# wifi_lamp_01.net
KiCad netlist of a schematic drawn in Altium Designer
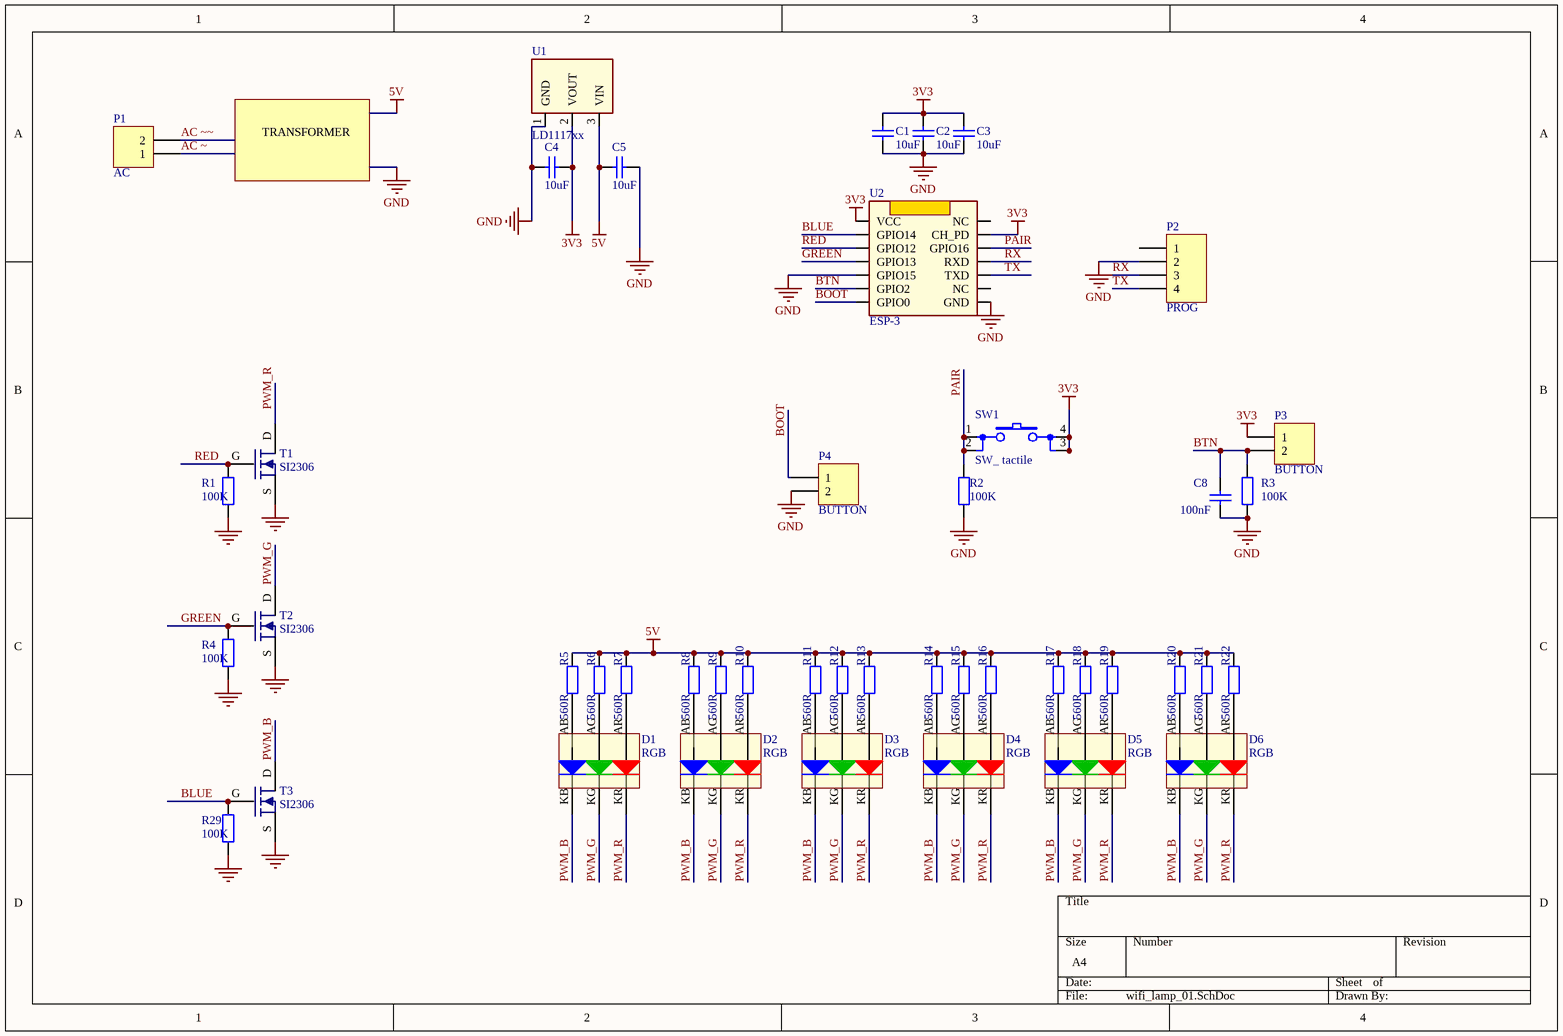
[diagram p0: wifi_lamp_01.SchDoc]

(export (version "E")
  (design (tool "Eeschema 10.0.6"))
  (components
    (comp (ref "C1")
      (value "10uF")
      (footprint "FP_1206_CAP_085")
      (description "Capacitor")
      (fields (field (name "PUBLISHER") "Altium Limited"))
      (libsource (lib "Miscellaneous Devices") (part "Cap"))
    )
    (comp (ref "C2")
      (value "10uF")
      (footprint "FP_1206_CAP_085")
      (description "Capacitor")
      (fields (field (name "PUBLISHER") "Altium Limited"))
      (libsource (lib "Miscellaneous Devices") (part "Cap"))
    )
    (comp (ref "C3")
      (value "10uF")
      (footprint "FP_1206_CAP_085")
      (description "Capacitor")
      (fields (field (name "PUBLISHER") "Altium Limited"))
      (libsource (lib "Miscellaneous Devices") (part "Cap"))
    )
    (comp (ref "C4")
      (value "10uF")
      (footprint "FP_1206_CAP_085")
      (description "Capacitor")
      (fields (field (name "PUBLISHER") "Altium Limited"))
      (libsource (lib "Miscellaneous Devices") (part "Cap"))
    )
    (comp (ref "C5")
      (value "10uF")
      (footprint "FP_1206_CAP_085")
      (description "Capacitor")
      (fields (field (name "PUBLISHER") "Altium Limited"))
      (libsource (lib "Miscellaneous Devices") (part "Cap"))
    )
    (comp (ref "C8")
      (value "100nF")
      (footprint "FP_0603_CAP_080")
      (description "Capacitor")
      (libsource (lib "Miscellaneous Devices") (part "Cap"))
    )
    (comp (ref "D1")
      (value "RGB")
      (footprint "RGB_LED_5.0x5.0mm")
      (description "LED_RGB_6_PIN")
      (libsource (lib "Led_optical") (part "LED_RGB_6_PIN"))
    )
    (comp (ref "D2")
      (value "RGB")
      (footprint "RGB_LED_5.0x5.0mm")
      (description "LED_RGB_6_PIN")
      (libsource (lib "Led_optical") (part "LED_RGB_6_PIN"))
    )
    (comp (ref "D3")
      (value "RGB")
      (footprint "RGB_LED_5.0x5.0mm")
      (description "LED_RGB_6_PIN")
      (libsource (lib "Led_optical") (part "LED_RGB_6_PIN"))
    )
    (comp (ref "D4")
      (value "RGB")
      (footprint "RGB_LED_5.0x5.0mm")
      (description "LED_RGB_6_PIN")
      (libsource (lib "Led_optical") (part "LED_RGB_6_PIN"))
    )
    (comp (ref "D5")
      (value "RGB")
      (footprint "RGB_LED_5.0x5.0mm")
      (description "LED_RGB_6_PIN")
      (libsource (lib "Led_optical") (part "LED_RGB_6_PIN"))
    )
    (comp (ref "D6")
      (value "RGB")
      (footprint "RGB_LED_5.0x5.0mm")
      (description "LED_RGB_6_PIN")
      (libsource (lib "Led_optical") (part "LED_RGB_6_PIN"))
    )
    (comp (ref "P1")
      (value "AC")
      (footprint "Sorkapocs 2P 5mm")
      (description "Header, 2-Pin")
      (fields (field (name "PUBLISHER") "Altium Limited"))
      (libsource (lib "") (part "Header 2_1"))
    )
    (comp (ref "P2")
      (value "PROG")
      (footprint "HDR1X4")
      (description "Header, 4-Pin")
      (fields (field (name "PUBLISHER") "Altium Limited"))
      (libsource (lib "Miscellaneous Connectors") (part "Header 4"))
    )
    (comp (ref "P3")
      (value "BUTTON")
      (footprint "HDR1X2")
      (description "Header, 2-Pin")
      (fields (field (name "PUBLISHER") "Altium Limited"))
      (libsource (lib "Miscellaneous Connectors") (part "Header 2"))
    )
    (comp (ref "P4")
      (value "BUTTON")
      (footprint "HDR1X2")
      (description "Header, 2-Pin")
      (fields (field (name "PUBLISHER") "Altium Limited"))
      (libsource (lib "Miscellaneous Connectors") (part "Header 2"))
    )
    (comp (ref "R1")
      (value "100K")
      (footprint "FP_0603_RES")
      (description "Resistor")
      (libsource (lib "Resistor") (part "RES"))
    )
    (comp (ref "R2")
      (value "100K")
      (footprint "FP_0603_RES")
      (description "Resistor")
      (libsource (lib "") (part "RES_1"))
    )
    (comp (ref "R3")
      (value "100K")
      (footprint "FP_0603_RES")
      (description "Resistor")
      (libsource (lib "Resistor") (part "RES"))
    )
    (comp (ref "R4")
      (value "100K")
      (footprint "FP_0603_RES")
      (description "Resistor")
      (libsource (lib "Resistor") (part "RES"))
    )
    (comp (ref "R5")
      (value "560R")
      (footprint "FP_0603_RES")
      (description "Resistor")
      (libsource (lib "Miscellaneous Devices") (part "Res3"))
    )
    (comp (ref "R6")
      (value "560R")
      (footprint "FP_0603_RES")
      (description "Resistor")
      (libsource (lib "Miscellaneous Devices") (part "Res3"))
    )
    (comp (ref "R7")
      (value "560R")
      (footprint "FP_0603_RES")
      (description "Resistor")
      (libsource (lib "Miscellaneous Devices") (part "Res3"))
    )
    (comp (ref "R8")
      (value "560R")
      (footprint "FP_0603_RES")
      (description "Resistor")
      (libsource (lib "Miscellaneous Devices") (part "Res3"))
    )
    (comp (ref "R9")
      (value "560R")
      (footprint "FP_0603_RES")
      (description "Resistor")
      (libsource (lib "Miscellaneous Devices") (part "Res3"))
    )
    (comp (ref "R10")
      (value "560R")
      (footprint "FP_0603_RES")
      (description "Resistor")
      (libsource (lib "Miscellaneous Devices") (part "Res3"))
    )
    (comp (ref "R11")
      (value "560R")
      (footprint "FP_0603_RES")
      (description "Resistor")
      (libsource (lib "Miscellaneous Devices") (part "Res3"))
    )
    (comp (ref "R12")
      (value "560R")
      (footprint "FP_0603_RES")
      (description "Resistor")
      (libsource (lib "Miscellaneous Devices") (part "Res3"))
    )
    (comp (ref "R13")
      (value "560R")
      (footprint "FP_0603_RES")
      (description "Resistor")
      (libsource (lib "Miscellaneous Devices") (part "Res3"))
    )
    (comp (ref "R14")
      (value "560R")
      (footprint "FP_0603_RES")
      (description "Resistor")
      (libsource (lib "Miscellaneous Devices") (part "Res3"))
    )
    (comp (ref "R15")
      (value "560R")
      (footprint "FP_0603_RES")
      (description "Resistor")
      (libsource (lib "Miscellaneous Devices") (part "Res3"))
    )
    (comp (ref "R16")
      (value "560R")
      (footprint "FP_0603_RES")
      (description "Resistor")
      (libsource (lib "Miscellaneous Devices") (part "Res3"))
    )
    (comp (ref "R17")
      (value "560R")
      (footprint "FP_0603_RES")
      (description "Resistor")
      (libsource (lib "Miscellaneous Devices") (part "Res3"))
    )
    (comp (ref "R18")
      (value "560R")
      (footprint "FP_0603_RES")
      (description "Resistor")
      (libsource (lib "Miscellaneous Devices") (part "Res3"))
    )
    (comp (ref "R19")
      (value "560R")
      (footprint "FP_0603_RES")
      (description "Resistor")
      (libsource (lib "Miscellaneous Devices") (part "Res3"))
    )
    (comp (ref "R20")
      (value "560R")
      (footprint "FP_0603_RES")
      (description "Resistor")
      (libsource (lib "Miscellaneous Devices") (part "Res3"))
    )
    (comp (ref "R21")
      (value "560R")
      (footprint "FP_0603_RES")
      (description "Resistor")
      (libsource (lib "Miscellaneous Devices") (part "Res3"))
    )
    (comp (ref "R22")
      (value "560R")
      (footprint "FP_0603_RES")
      (description "Resistor")
      (libsource (lib "Miscellaneous Devices") (part "Res3"))
    )
    (comp (ref "R29")
      (value "100K")
      (footprint "FP_0603_RES")
      (description "Resistor")
      (libsource (lib "Resistor") (part "RES"))
    )
    (comp (ref "SW1")
      (value "SW_ tactile")
      (footprint "FP_TACTBTN")
      (libsource (lib "Switch") (part "SW_ tactile"))
    )
    (comp (ref "T1") (value "SI2306") (footprint "FET_SOT23") (libsource (lib "FET") (part "NMOS")))
    (comp (ref "T2") (value "SI2306") (footprint "FET_SOT23") (libsource (lib "FET") (part "NMOS")))
    (comp (ref "T3") (value "SI2306") (footprint "FET_SOT23") (libsource (lib "FET") (part "NMOS")))
    (comp (ref "U1")
      (value "LD1117xx")
      (footprint "SUPPLY_SOT223")
      (description "LD1117xx 3,3V lin reg")
      (libsource (lib "Supply") (part "LD1117xx"))
    )
    (comp (ref "U2")
      (value "ESP-3")
      (footprint "ESP_3")
      (description "ESP-3wifi module")
      (libsource (lib "Modul") (part "ESP-3"))
    )
  )
  (nets
    (net (code "1") (name "/AC ~") (class "Default")
      (node (ref "P1") (pin "1") (pinfunction "1_1") (pintype "passive"))
    )
    (net (code "2") (name "/AC ~~") (class "Default")
      (node (ref "P1") (pin "2") (pinfunction "2_2") (pintype "passive"))
    )
    (net (code "3") (name "/BLUE") (class "Default")
      (node (ref "R29") (pin "2") (pinfunction "2_2") (pintype "passive"))
      (node (ref "T3") (pin "G") (pinfunction "G_G") (pintype "passive"))
      (node (ref "U2") (pin "2") (pinfunction "GPIO14_2") (pintype "passive"))
    )
    (net (code "4") (name "/BOOT") (class "Default")
      (node (ref "P4") (pin "1") (pinfunction "1_1") (pintype "passive"))
      (node (ref "U2") (pin "7") (pinfunction "GPIO0_7") (pintype "passive"))
    )
    (net (code "5") (name "/BTN") (class "Default")
      (node (ref "C8") (pin "1") (pinfunction "1_1") (pintype "passive"))
      (node (ref "P3") (pin "2") (pinfunction "2_2") (pintype "passive"))
      (node (ref "R3") (pin "2") (pinfunction "2_2") (pintype "passive"))
      (node (ref "U2") (pin "6") (pinfunction "GPIO2_6") (pintype "passive"))
    )
    (net (code "6") (name "/GREEN") (class "Default")
      (node (ref "R4") (pin "2") (pinfunction "2_2") (pintype "passive"))
      (node (ref "T2") (pin "G") (pinfunction "G_G") (pintype "passive"))
      (node (ref "U2") (pin "4") (pinfunction "GPIO13_4") (pintype "passive"))
    )
    (net (code "7") (name "/PAIR") (class "Default")
      (node (ref "R2") (pin "1") (pinfunction "1_1") (pintype "passive"))
      (node (ref "SW1") (pin "1") (pinfunction "1_1") (pintype "passive"))
      (node (ref "SW1") (pin "2") (pinfunction "2_2") (pintype "passive"))
      (node (ref "U2") (pin "12") (pinfunction "GPIO16_12") (pintype "passive"))
    )
    (net (code "8") (name "/PWM_B") (class "Default")
      (node (ref "D1") (pin "KB") (pinfunction "R_KB") (pintype "passive"))
      (node (ref "D2") (pin "KB") (pinfunction "R_KB") (pintype "passive"))
      (node (ref "D3") (pin "KB") (pinfunction "R_KB") (pintype "passive"))
      (node (ref "D4") (pin "KB") (pinfunction "R_KB") (pintype "passive"))
      (node (ref "D5") (pin "KB") (pinfunction "R_KB") (pintype "passive"))
      (node (ref "D6") (pin "KB") (pinfunction "R_KB") (pintype "passive"))
      (node (ref "T3") (pin "D") (pinfunction "D_D") (pintype "passive"))
    )
    (net (code "9") (name "/PWM_G") (class "Default")
      (node (ref "D1") (pin "KG") (pinfunction "G_KG") (pintype "passive"))
      (node (ref "D2") (pin "KG") (pinfunction "G_KG") (pintype "passive"))
      (node (ref "D3") (pin "KG") (pinfunction "G_KG") (pintype "passive"))
      (node (ref "D4") (pin "KG") (pinfunction "G_KG") (pintype "passive"))
      (node (ref "D5") (pin "KG") (pinfunction "G_KG") (pintype "passive"))
      (node (ref "D6") (pin "KG") (pinfunction "G_KG") (pintype "passive"))
      (node (ref "T2") (pin "D") (pinfunction "D_D") (pintype "passive"))
    )
    (net (code "10") (name "/PWM_R") (class "Default")
      (node (ref "D1") (pin "KR") (pinfunction "B_KR") (pintype "passive"))
      (node (ref "D2") (pin "KR") (pinfunction "B_KR") (pintype "passive"))
      (node (ref "D3") (pin "KR") (pinfunction "B_KR") (pintype "passive"))
      (node (ref "D4") (pin "KR") (pinfunction "B_KR") (pintype "passive"))
      (node (ref "D5") (pin "KR") (pinfunction "B_KR") (pintype "passive"))
      (node (ref "D6") (pin "KR") (pinfunction "B_KR") (pintype "passive"))
      (node (ref "T1") (pin "D") (pinfunction "D_D") (pintype "passive"))
    )
    (net (code "11") (name "/RED") (class "Default")
      (node (ref "R1") (pin "2") (pinfunction "2_2") (pintype "passive"))
      (node (ref "T1") (pin "G") (pinfunction "G_G") (pintype "passive"))
      (node (ref "U2") (pin "3") (pinfunction "GPIO12_3") (pintype "passive"))
    )
    (net (code "12") (name "/RX") (class "Default")
      (node (ref "P2") (pin "3") (pinfunction "3_3") (pintype "passive"))
      (node (ref "U2") (pin "11") (pinfunction "RXD_11") (pintype "passive"))
    )
    (net (code "13") (name "/TX") (class "Default")
      (node (ref "P2") (pin "4") (pinfunction "4_4") (pintype "passive"))
      (node (ref "U2") (pin "10") (pinfunction "TXD_10") (pintype "passive"))
    )
    (net (code "14") (name "3V3") (class "Default")
      (node (ref "C1") (pin "2") (pinfunction "2_2") (pintype "passive"))
      (node (ref "C2") (pin "2") (pinfunction "2_2") (pintype "passive"))
      (node (ref "C3") (pin "2") (pinfunction "2_2") (pintype "passive"))
      (node (ref "C4") (pin "2") (pinfunction "2_2") (pintype "passive"))
      (node (ref "P3") (pin "1") (pinfunction "1_1") (pintype "passive"))
      (node (ref "SW1") (pin "3") (pinfunction "3_3") (pintype "passive"))
      (node (ref "SW1") (pin "4") (pinfunction "4_4") (pintype "passive"))
      (node (ref "U1") (pin "2") (pinfunction "VOUT_2") (pintype "passive"))
      (node (ref "U2") (pin "1") (pinfunction "VCC_1") (pintype "passive"))
      (node (ref "U2") (pin "13") (pinfunction "CH_PD_13") (pintype "passive"))
    )
    (net (code "15") (name "5V") (class "Default")
      (node (ref "C5") (pin "1") (pinfunction "1_1") (pintype "passive"))
      (node (ref "R10") (pin "2") (pinfunction "2_2") (pintype "passive"))
      (node (ref "R11") (pin "2") (pinfunction "2_2") (pintype "passive"))
      (node (ref "R12") (pin "2") (pinfunction "2_2") (pintype "passive"))
      (node (ref "R13") (pin "2") (pinfunction "2_2") (pintype "passive"))
      (node (ref "R14") (pin "2") (pinfunction "2_2") (pintype "passive"))
      (node (ref "R15") (pin "2") (pinfunction "2_2") (pintype "passive"))
      (node (ref "R16") (pin "2") (pinfunction "2_2") (pintype "passive"))
      (node (ref "R17") (pin "2") (pinfunction "2_2") (pintype "passive"))
      (node (ref "R18") (pin "2") (pinfunction "2_2") (pintype "passive"))
      (node (ref "R19") (pin "2") (pinfunction "2_2") (pintype "passive"))
      (node (ref "R20") (pin "2") (pinfunction "2_2") (pintype "passive"))
      (node (ref "R21") (pin "2") (pinfunction "2_2") (pintype "passive"))
      (node (ref "R22") (pin "2") (pinfunction "2_2") (pintype "passive"))
      (node (ref "R5") (pin "2") (pinfunction "2_2") (pintype "passive"))
      (node (ref "R6") (pin "2") (pinfunction "2_2") (pintype "passive"))
      (node (ref "R7") (pin "2") (pinfunction "2_2") (pintype "passive"))
      (node (ref "R8") (pin "2") (pinfunction "2_2") (pintype "passive"))
      (node (ref "R9") (pin "2") (pinfunction "2_2") (pintype "passive"))
      (node (ref "U1") (pin "3") (pinfunction "VIN_3") (pintype "passive"))
    )
    (net (code "16") (name "GND") (class "Default")
      (node (ref "C1") (pin "1") (pinfunction "1_1") (pintype "passive"))
      (node (ref "C2") (pin "1") (pinfunction "1_1") (pintype "passive"))
      (node (ref "C3") (pin "1") (pinfunction "1_1") (pintype "passive"))
      (node (ref "C4") (pin "1") (pinfunction "1_1") (pintype "passive"))
      (node (ref "C5") (pin "2") (pinfunction "2_2") (pintype "passive"))
      (node (ref "C8") (pin "2") (pinfunction "2_2") (pintype "passive"))
      (node (ref "P2") (pin "2") (pinfunction "2_2") (pintype "passive"))
      (node (ref "P4") (pin "2") (pinfunction "2_2") (pintype "passive"))
      (node (ref "R1") (pin "1") (pinfunction "1_1") (pintype "passive"))
      (node (ref "R2") (pin "2") (pinfunction "2_2") (pintype "passive"))
      (node (ref "R29") (pin "1") (pinfunction "1_1") (pintype "passive"))
      (node (ref "R3") (pin "1") (pinfunction "1_1") (pintype "passive"))
      (node (ref "R4") (pin "1") (pinfunction "1_1") (pintype "passive"))
      (node (ref "T1") (pin "S") (pinfunction "S_S") (pintype "passive"))
      (node (ref "T2") (pin "S") (pinfunction "S_S") (pintype "passive"))
      (node (ref "T3") (pin "S") (pinfunction "S_S") (pintype "passive"))
      (node (ref "U1") (pin "1") (pinfunction "GND_1") (pintype "passive"))
      (node (ref "U2") (pin "5") (pinfunction "GPIO15_5") (pintype "passive"))
      (node (ref "U2") (pin "8") (pinfunction "GND_8") (pintype "passive"))
    )
    (net (code "17") (name "Net-(D1-A-PadAB)") (class "Default")
      (node (ref "D1") (pin "AB") (pinfunction "A_AB") (pintype "passive"))
      (node (ref "R5") (pin "1") (pinfunction "1_1") (pintype "passive"))
    )
    (net (code "18") (name "Net-(D1-A-PadAG)") (class "Default")
      (node (ref "D1") (pin "AG") (pinfunction "A_AG") (pintype "passive"))
      (node (ref "R6") (pin "1") (pinfunction "1_1") (pintype "passive"))
    )
    (net (code "19") (name "Net-(D1-A-PadAR)") (class "Default")
      (node (ref "D1") (pin "AR") (pinfunction "A_AR") (pintype "passive"))
      (node (ref "R7") (pin "1") (pinfunction "1_1") (pintype "passive"))
    )
    (net (code "20") (name "Net-(D2-A-PadAB)") (class "Default")
      (node (ref "D2") (pin "AB") (pinfunction "A_AB") (pintype "passive"))
      (node (ref "R8") (pin "1") (pinfunction "1_1") (pintype "passive"))
    )
    (net (code "21") (name "Net-(D2-A-PadAG)") (class "Default")
      (node (ref "D2") (pin "AG") (pinfunction "A_AG") (pintype "passive"))
      (node (ref "R9") (pin "1") (pinfunction "1_1") (pintype "passive"))
    )
    (net (code "22") (name "Net-(D2-A-PadAR)") (class "Default")
      (node (ref "D2") (pin "AR") (pinfunction "A_AR") (pintype "passive"))
      (node (ref "R10") (pin "1") (pinfunction "1_1") (pintype "passive"))
    )
    (net (code "23") (name "Net-(D3-A-PadAB)") (class "Default")
      (node (ref "D3") (pin "AB") (pinfunction "A_AB") (pintype "passive"))
      (node (ref "R11") (pin "1") (pinfunction "1_1") (pintype "passive"))
    )
    (net (code "24") (name "Net-(D3-A-PadAG)") (class "Default")
      (node (ref "D3") (pin "AG") (pinfunction "A_AG") (pintype "passive"))
      (node (ref "R12") (pin "1") (pinfunction "1_1") (pintype "passive"))
    )
    (net (code "25") (name "Net-(D3-A-PadAR)") (class "Default")
      (node (ref "D3") (pin "AR") (pinfunction "A_AR") (pintype "passive"))
      (node (ref "R13") (pin "1") (pinfunction "1_1") (pintype "passive"))
    )
    (net (code "26") (name "Net-(D4-A-PadAB)") (class "Default")
      (node (ref "D4") (pin "AB") (pinfunction "A_AB") (pintype "passive"))
      (node (ref "R14") (pin "1") (pinfunction "1_1") (pintype "passive"))
    )
    (net (code "27") (name "Net-(D4-A-PadAG)") (class "Default")
      (node (ref "D4") (pin "AG") (pinfunction "A_AG") (pintype "passive"))
      (node (ref "R15") (pin "1") (pinfunction "1_1") (pintype "passive"))
    )
    (net (code "28") (name "Net-(D4-A-PadAR)") (class "Default")
      (node (ref "D4") (pin "AR") (pinfunction "A_AR") (pintype "passive"))
      (node (ref "R16") (pin "1") (pinfunction "1_1") (pintype "passive"))
    )
    (net (code "29") (name "Net-(D5-A-PadAB)") (class "Default")
      (node (ref "D5") (pin "AB") (pinfunction "A_AB") (pintype "passive"))
      (node (ref "R17") (pin "1") (pinfunction "1_1") (pintype "passive"))
    )
    (net (code "30") (name "Net-(D5-A-PadAG)") (class "Default")
      (node (ref "D5") (pin "AG") (pinfunction "A_AG") (pintype "passive"))
      (node (ref "R18") (pin "1") (pinfunction "1_1") (pintype "passive"))
    )
    (net (code "31") (name "Net-(D5-A-PadAR)") (class "Default")
      (node (ref "D5") (pin "AR") (pinfunction "A_AR") (pintype "passive"))
      (node (ref "R19") (pin "1") (pinfunction "1_1") (pintype "passive"))
    )
    (net (code "32") (name "Net-(D6-A-PadAB)") (class "Default")
      (node (ref "D6") (pin "AB") (pinfunction "A_AB") (pintype "passive"))
      (node (ref "R20") (pin "1") (pinfunction "1_1") (pintype "passive"))
    )
    (net (code "33") (name "Net-(D6-A-PadAG)") (class "Default")
      (node (ref "D6") (pin "AG") (pinfunction "A_AG") (pintype "passive"))
      (node (ref "R21") (pin "1") (pinfunction "1_1") (pintype "passive"))
    )
    (net (code "34") (name "Net-(D6-A-PadAR)") (class "Default")
      (node (ref "D6") (pin "AR") (pinfunction "A_AR") (pintype "passive"))
      (node (ref "R22") (pin "1") (pinfunction "1_1") (pintype "passive"))
    )
    (net (code "35") (name "unconnected-(P2-Pad1)") (class "Default")
      (node (ref "P2") (pin "1") (pinfunction "1_1") (pintype "passive"))
    )
    (net (code "36") (name "unconnected-(U2-NC-Pad9)") (class "Default")
      (node (ref "U2") (pin "9") (pinfunction "NC_9") (pintype "passive"))
    )
    (net (code "37") (name "unconnected-(U2-NC-Pad14)") (class "Default")
      (node (ref "U2") (pin "14") (pinfunction "NC_14") (pintype "passive"))
    )
  )
)
